# mcu.net
KiCad netlist of a schematic drawn in Altium Designer
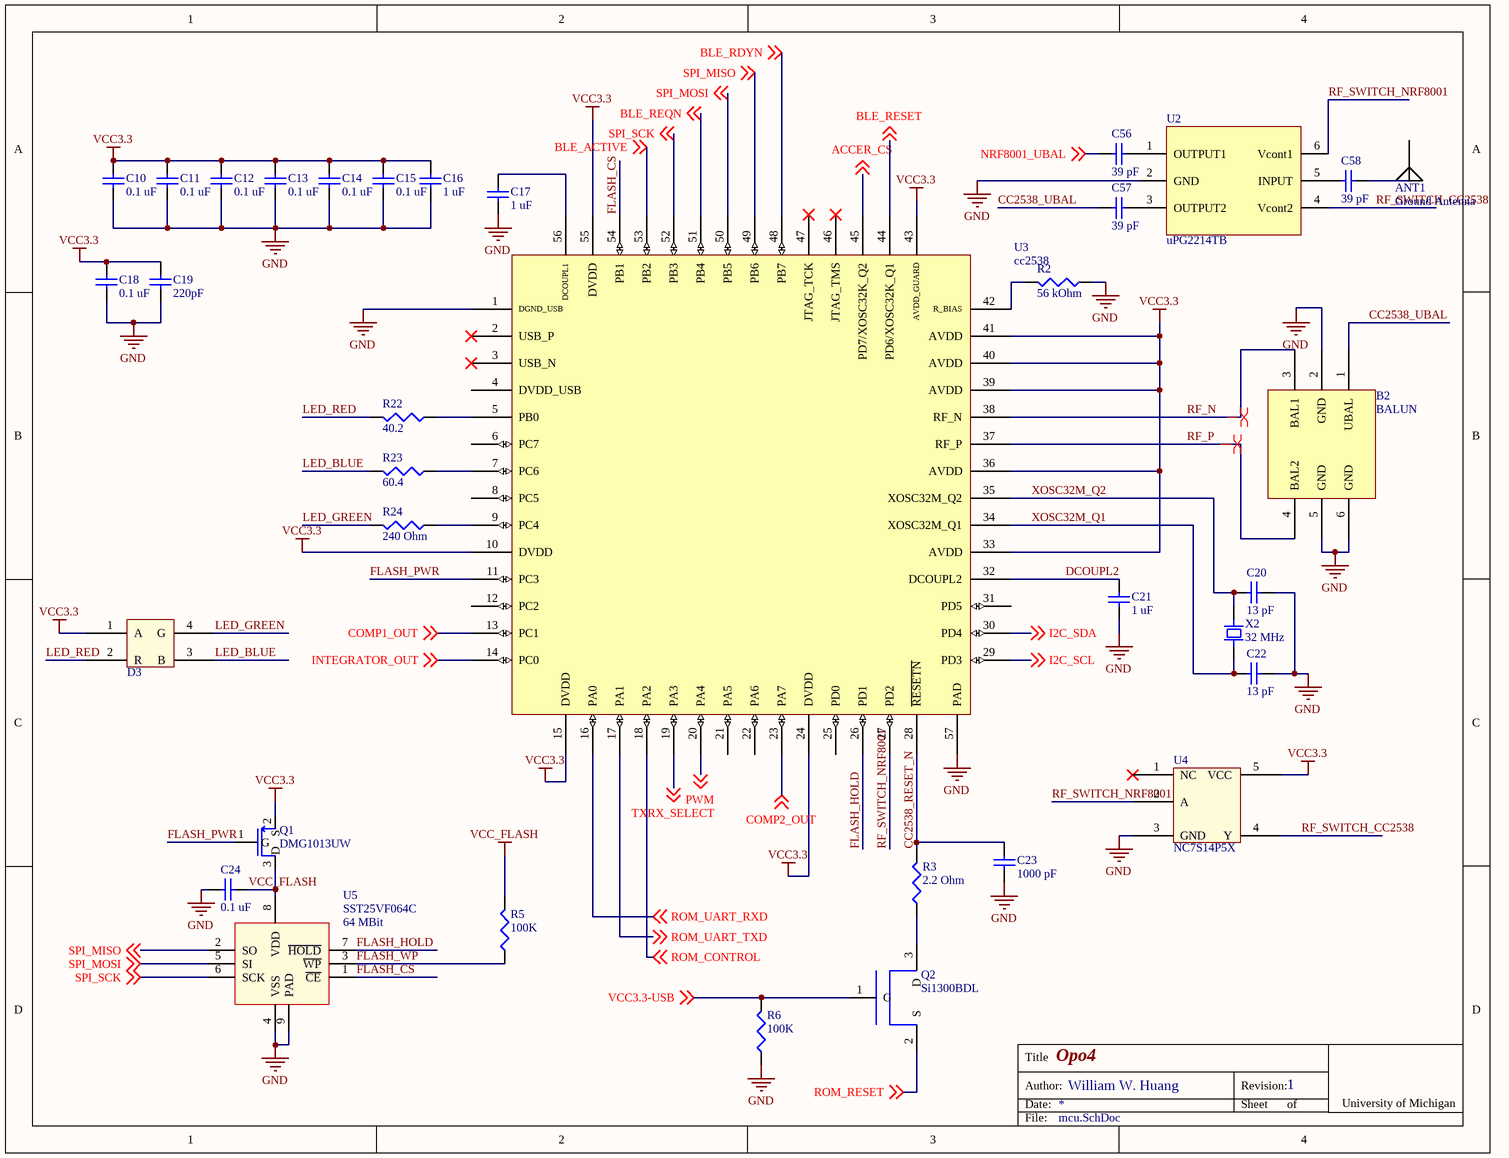
[diagram p0: mcu.SchDoc]

(export (version "E")
  (design (tool "Eeschema 10.0.6"))
  (components
    (comp (ref "ANT1")
      (value "Ground Antenna")
      (footprint "SMD Ground Antenna")
      (description "Molex 2.4 GHz SMD On-Ground Antenna")
      (libsource (lib "opo_general") (part "Molex Antenna"))
    )
    (comp (ref "B2")
      (value "BALUN")
      (footprint "2450BM15A0002")
      (description "Johanson CC253X Balun")
      (fields (field (name "MFR") "Johanson Technology") (field (name "MFR PART NUMBER") "2450BM15A0002"))
      (libsource (lib "opo_general") (part "cc2538_Balun"))
    )
    (comp (ref "C10")
      (value "0.1 uF")
      (footprint "0402")
      (description "Ceramic capacitor, 0.1u, 0402 package")
      (fields (field (name "TOLERANCE") "10%") (field (name "Comment") "Ceramic capacitor"))
      (libsource (lib "rlc") (part "C_0.1u_0402_ceramic"))
    )
    (comp (ref "C11")
      (value "0.1 uF")
      (footprint "0402")
      (description "Ceramic capacitor, 0.1u, 0402 package")
      (fields (field (name "TOLERANCE") "10%") (field (name "Comment") "Ceramic capacitor"))
      (libsource (lib "rlc") (part "C_0.1u_0402_ceramic"))
    )
    (comp (ref "C12")
      (value "0.1 uF")
      (footprint "0402")
      (description "Ceramic capacitor, 0.1u, 0402 package")
      (fields (field (name "TOLERANCE") "10%") (field (name "Comment") "Ceramic capacitor"))
      (libsource (lib "rlc") (part "C_0.1u_0402_ceramic"))
    )
    (comp (ref "C13")
      (value "0.1 uF")
      (footprint "0402")
      (description "Ceramic capacitor, 0.1u, 0402 package")
      (fields (field (name "TOLERANCE") "10%") (field (name "Comment") "Ceramic capacitor"))
      (libsource (lib "rlc") (part "C_0.1u_0402_ceramic"))
    )
    (comp (ref "C14")
      (value "0.1 uF")
      (footprint "0402")
      (description "Ceramic capacitor, 0.1u, 0402 package")
      (fields (field (name "TOLERANCE") "10%") (field (name "Comment") "Ceramic capacitor"))
      (libsource (lib "rlc") (part "C_0.1u_0402_ceramic"))
    )
    (comp (ref "C15")
      (value "0.1 uF")
      (footprint "0402")
      (description "Ceramic capacitor, 0.1u, 0402 package")
      (fields (field (name "TOLERANCE") "10%") (field (name "Comment") "Ceramic capacitor"))
      (libsource (lib "rlc") (part "C_0.1u_0402_ceramic"))
    )
    (comp (ref "C16")
      (value "1 uF")
      (footprint "0402")
      (description "Ceramic capacitor, 1 uF, 0402 package")
      (fields (field (name "TOLERANCE") "10%") (field (name "Comment") "Ceramic capacitor"))
      (libsource (lib "rlc") (part "C_1u_0402_ceramic"))
    )
    (comp (ref "C17")
      (value "1 uF")
      (footprint "0402")
      (description "Ceramic capacitor, 1 uF, 0402 package")
      (fields (field (name "TOLERANCE") "10%") (field (name "Comment") "Ceramic capacitor"))
      (libsource (lib "rlc") (part "C_1u_0402_ceramic"))
    )
    (comp (ref "C18")
      (value "0.1 uF")
      (footprint "0402")
      (description "Ceramic capacitor, 0.1u, 0402 package")
      (fields (field (name "TOLERANCE") "10%") (field (name "Comment") "Ceramic capacitor"))
      (libsource (lib "rlc") (part "C_0.1u_0402_ceramic"))
    )
    (comp (ref "C19")
      (value "220pF")
      (footprint "0402")
      (description "220pF 5% 50 V C0G NP0 0402 ceramic cap")
      (fields (field (name "MFR") "Murata") (field (name "MFR PART NUMBER") "GRM1555C1H221JA01D"))
      (libsource (lib "rlc") (part "C_220pf_0402_ceramic"))
    )
    (comp (ref "C20")
      (value "13 pF")
      (footprint "0402")
      (description "13pf, 50V, 2%, c0G, NP0, 0402, ceramic")
      (fields (field (name "MFR") "Murata") (field (name "MFR PART NUMBER") "GRM1555C1H130GA01D"))
      (libsource (lib "rlc") (part "C_13p_0402"))
    )
    (comp (ref "C21")
      (value "1 uF")
      (footprint "0402")
      (description "Ceramic capacitor, 1 uF, 0402 package")
      (fields (field (name "TOLERANCE") "10%") (field (name "Comment") "Ceramic capacitor"))
      (libsource (lib "rlc") (part "C_1u_0402_ceramic"))
    )
    (comp (ref "C22")
      (value "13 pF")
      (footprint "0402")
      (description "13pf, 50V, 2%, c0G, NP0, 0402, ceramic")
      (fields (field (name "MFR") "Murata") (field (name "MFR PART NUMBER") "GRM1555C1H130GA01D"))
      (libsource (lib "rlc") (part "C_13p_0402"))
    )
    (comp (ref "C23")
      (value "1000 pF")
      (footprint "0402")
      (description "Ceramic capacitor, 1000 pF, 0402 package")
      (fields (field (name "TOLERANCE") "10%") (field (name "Comment") "Ceramic capacitor"))
      (libsource (lib "rlc") (part "C_1000p_0402_ceramic"))
    )
    (comp (ref "C24")
      (value "0.1 uF")
      (footprint "0402")
      (description "Ceramic capacitor, 0.1u, 0402 package")
      (fields (field (name "TOLERANCE") "10%") (field (name "Comment") "Ceramic capacitor"))
      (libsource (lib "rlc") (part "C_0.1u_0402_ceramic"))
    )
    (comp (ref "C56")
      (value "39 pF")
      (footprint "0402")
      (description "Ceramic capacitor, 0402, 39 pF, 5%, C0G, NP0, RF suitable")
      (fields (field (name "Comment") "Ceramic Capacitor"))
      (libsource (lib "rlc") (part "C_39pf_0402_ceramic"))
    )
    (comp (ref "C57")
      (value "39 pF")
      (footprint "0402")
      (description "Ceramic capacitor, 0402, 39 pF, 5%, C0G, NP0, RF suitable")
      (fields (field (name "Comment") "Ceramic Capacitor"))
      (libsource (lib "rlc") (part "C_39pf_0402_ceramic"))
    )
    (comp (ref "C58")
      (value "39 pF")
      (footprint "0402")
      (description "Ceramic capacitor, 0402, 39 pF, 5%, C0G, NP0, RF suitable")
      (fields (field (name "Comment") "Ceramic Capacitor"))
      (libsource (lib "rlc") (part "C_39pf_0402_ceramic"))
    )
    (comp (ref "D3")
      (value "Tri Color LED")
      (footprint "0404")
      (description "LED, RGB, 0404")
      (libsource (lib "rlc") (part "D_LED_RGB_0404"))
    )
    (comp (ref "Q1")
      (value "DMG1013UW")
      (footprint "SC70-3")
      (description "P-CHANNEL ENHANCEMENT MODE MOSFET")
      (libsource (lib "opo_general") (part "DMG1013UW"))
    )
    (comp (ref "Q2")
      (value "Si1300BDL")
      (footprint "SC70-3")
      (description "MOSFET N-CH D-S 20V SC-70-3")
      (libsource (lib "opo_general") (part "Si1300BDL"))
    )
    (comp (ref "R2")
      (value "56 kOhm")
      (footprint "0402")
      (description "56 kOhm, 1%, .0603 W, 0402")
      (fields (field (name "MFR") "Rohm") (field (name "MFR PART NUMBER") "MCR01MRTF5602"))
      (libsource (lib "rlc") (part "R_56K_0402"))
    )
    (comp (ref "R3")
      (value "2.2 Ohm")
      (footprint "0402")
      (description "2.2 Ohm, 1%, .063W, 0402")
      (fields (field (name "MFR") "Vishay Dale") (field (name "MFR PART NUMBER") "CRCW04022R20FKED"))
      (libsource (lib "rlc") (part "R_2.2_0402"))
    )
    (comp (ref "R5")
      (value "100K")
      (footprint "0402")
      (description "Chip resistor, 100K, 0402 package")
      (fields (field (name "TOLERANCE") "1%") (field (name "POWER") "1/16 W"))
      (libsource (lib "rlc") (part "R_100K_0402"))
    )
    (comp (ref "R6")
      (value "100K")
      (footprint "0402")
      (description "Chip resistor, 100K, 0402 package")
      (fields (field (name "TOLERANCE") "1%") (field (name "POWER") "1/16 W"))
      (libsource (lib "rlc") (part "R_100K_0402"))
    )
    (comp (ref "R22")
      (value "40.2")
      (footprint "0201")
      (description "40.2 Ohm 0201 1% Chip Resistor")
      (fields (field (name "Comment") "Chip Resistor"))
      (libsource (lib "rlc") (part "R_40.2_0201"))
    )
    (comp (ref "R23")
      (value "60.4")
      (footprint "0201")
      (description "60.4 Ohm, .05W, 1% 0201 Chip Resistor")
      (fields (field (name "Comment") "Chip resistor"))
      (libsource (lib "rlc") (part "R_60.4_0201"))
    )
    (comp (ref "R24")
      (value "240 Ohm")
      (footprint "0201")
      (description "240 Ohm, 1%, .05W, 0201 Chip Resistor")
      (fields (field (name "Comment") "Chip resistor"))
      (libsource (lib "rlc") (part "R_240_0201"))
    )
    (comp (ref "U2")
      (value "uPG2214TB")
      (footprint "minimold-6")
      (description "GaAs Integrated Circuit for L, S-Band SPDT Switch")
      (libsource (lib "opo_general") (part "uPG2214TB"))
    )
    (comp (ref "U3")
      (value "cc2538")
      (footprint "QFN50P800X800X100_HS-57N")
      (description "cc2538 MCU/802.15.4 radio")
      (libsource (lib "opo_general") (part "cc2538"))
    )
    (comp (ref "U4")
      (value "NC7S14P5X")
      (footprint "SC70-5")
      (description "Single Inverter")
      (fields (field (name "MFR") "Fairchild"))
      (libsource (lib "opo_general") (part "NC7S14P5X"))
    )
    (comp (ref "U5")
      (value "SST25VF064C")
      (footprint "WSON")
      (description "64 Mbit SPI Serial Dual I/O Flash")
      (fields (field (name "CAPACITY") "64 MBit"))
      (libsource (lib "opo_general") (part "SST25VF064C"))
    )
    (comp (ref "X2")
      (value "32 MHz")
      (footprint "FA-128")
      (description "32MHz, 10ppm, 10pF, 60 Ohm")
      (fields (field (name "MFR") "Epson") (field (name "MFR PART NUMBER") "FA-128 32.0000MF20X-K3"))
      (libsource (lib "opo_general") (part "X_32M_FA-128"))
    )
  )
  (nets
    (net (code "1") (name "/CC2538_RESET_N") (class "Default")
      (node (ref "C23") (pin "1") (pintype "passive"))
      (node (ref "R3") (pin "1") (pintype "passive"))
      (node (ref "U3") (pin "28") (pinfunction "~{RESETN}_28") (pintype "passive"))
    )
    (net (code "2") (name "/CC2538_UBAL") (class "Default")
      (node (ref "B2") (pin "1") (pinfunction "UBAL_1") (pintype "passive"))
      (node (ref "C57") (pin "2") (pintype "passive"))
    )
    (net (code "3") (name "/DCOUPL2") (class "Default")
      (node (ref "C21") (pin "1") (pintype "passive"))
      (node (ref "U3") (pin "32") (pinfunction "DCOUPL2_32") (pintype "power_in"))
    )
    (net (code "4") (name "/FLASH_CS") (class "Default")
      (node (ref "U3") (pin "54") (pinfunction "PB1_54") (pintype "bidirectional"))
      (node (ref "U5") (pin "1") (pinfunction "~{CE}_1") (pintype "passive"))
    )
    (net (code "5") (name "/FLASH_HOLD") (class "Default")
      (node (ref "U3") (pin "26") (pinfunction "PD1_26") (pintype "bidirectional"))
      (node (ref "U5") (pin "7") (pinfunction "~{HOLD}_7") (pintype "passive"))
    )
    (net (code "6") (name "/FLASH_PWR") (class "Default")
      (node (ref "Q1") (pin "1") (pinfunction "G_1") (pintype "passive"))
      (node (ref "U3") (pin "11") (pinfunction "PC3_11") (pintype "bidirectional"))
    )
    (net (code "7") (name "/FLASH_WP") (class "Default")
      (node (ref "R5") (pin "2") (pintype "passive"))
      (node (ref "U5") (pin "3") (pinfunction "~{WP}_3") (pintype "passive"))
    )
    (net (code "8") (name "/LED_BLUE") (class "Default")
      (node (ref "D3") (pin "3") (pinfunction "B_3") (pintype "passive"))
      (node (ref "R23") (pin "1") (pintype "passive"))
    )
    (net (code "9") (name "/LED_GREEN") (class "Default")
      (node (ref "D3") (pin "4") (pinfunction "G_4") (pintype "passive"))
      (node (ref "R24") (pin "1") (pintype "passive"))
    )
    (net (code "10") (name "/LED_RED") (class "Default")
      (node (ref "D3") (pin "2") (pinfunction "R_2") (pintype "passive"))
      (node (ref "R22") (pin "1") (pintype "passive"))
    )
    (net (code "11") (name "/RF_N") (class "Default")
      (node (ref "B2") (pin "3") (pinfunction "BAL1_3") (pintype "passive"))
      (node (ref "U3") (pin "38") (pinfunction "RF_N_38") (pintype "passive"))
    )
    (net (code "12") (name "/RF_P") (class "Default")
      (node (ref "B2") (pin "4") (pinfunction "BAL2_4") (pintype "passive"))
      (node (ref "U3") (pin "37") (pinfunction "RF_P_37") (pintype "passive"))
    )
    (net (code "13") (name "/RF_SWITCH_CC2538") (class "Default")
      (node (ref "U2") (pin "4") (pinfunction "Vcont2_4") (pintype "power_in"))
      (node (ref "U4") (pin "4") (pinfunction "Y_4") (pintype "passive"))
    )
    (net (code "14") (name "/RF_SWITCH_NRF8001") (class "Default")
      (node (ref "U2") (pin "6") (pinfunction "Vcont1_6") (pintype "power_in"))
      (node (ref "U3") (pin "27") (pinfunction "PD2_27") (pintype "bidirectional"))
      (node (ref "U4") (pin "2") (pinfunction "A_2") (pintype "passive"))
    )
    (net (code "15") (name "/XOSC32M_Q1") (class "Default")
      (node (ref "C22") (pin "2") (pintype "passive"))
      (node (ref "U3") (pin "34") (pinfunction "XOSC32M_Q1_34") (pintype "passive"))
      (node (ref "X2") (pin "3") (pintype "passive"))
    )
    (net (code "16") (name "/XOSC32M_Q2") (class "Default")
      (node (ref "C20") (pin "1") (pintype "passive"))
      (node (ref "U3") (pin "35") (pinfunction "XOSC32M_Q2_35") (pintype "passive"))
      (node (ref "X2") (pin "1") (pintype "passive"))
    )
    (net (code "17") (name "ACCER_CS") (class "Default")
      (node (ref "U3") (pin "45") (pinfunction "PD7/XOSC32K_Q2_45") (pintype "passive"))
    )
    (net (code "18") (name "BLE_ACTIVE") (class "Default")
      (node (ref "U3") (pin "53") (pinfunction "PB2_53") (pintype "bidirectional"))
    )
    (net (code "19") (name "BLE_RDYN") (class "Default")
      (node (ref "U3") (pin "48") (pinfunction "PB7_48") (pintype "bidirectional"))
    )
    (net (code "20") (name "BLE_REQN") (class "Default")
      (node (ref "U3") (pin "51") (pinfunction "PB4_51") (pintype "bidirectional"))
    )
    (net (code "21") (name "BLE_RESET") (class "Default")
      (node (ref "U3") (pin "44") (pinfunction "PD6/XOSC32K_Q1_44") (pintype "passive"))
    )
    (net (code "22") (name "COMP1_OUT") (class "Default")
      (node (ref "U3") (pin "13") (pinfunction "PC1_13") (pintype "bidirectional"))
    )
    (net (code "23") (name "COMP2_OUT") (class "Default")
      (node (ref "U3") (pin "23") (pinfunction "PA7_23") (pintype "bidirectional"))
    )
    (net (code "24") (name "GND") (class "Default")
      (node (ref "B2") (pin "2") (pinfunction "GND_2") (pintype "passive"))
      (node (ref "B2") (pin "5") (pinfunction "GND_5") (pintype "passive"))
      (node (ref "B2") (pin "6") (pinfunction "GND_6") (pintype "passive"))
      (node (ref "C10") (pin "2") (pintype "passive"))
      (node (ref "C11") (pin "2") (pintype "passive"))
      (node (ref "C12") (pin "2") (pintype "passive"))
      (node (ref "C13") (pin "2") (pintype "passive"))
      (node (ref "C14") (pin "2") (pintype "passive"))
      (node (ref "C15") (pin "2") (pintype "passive"))
      (node (ref "C16") (pin "2") (pintype "passive"))
      (node (ref "C17") (pin "2") (pintype "passive"))
      (node (ref "C18") (pin "2") (pintype "passive"))
      (node (ref "C19") (pin "2") (pintype "passive"))
      (node (ref "C20") (pin "2") (pintype "passive"))
      (node (ref "C21") (pin "2") (pintype "passive"))
      (node (ref "C22") (pin "1") (pintype "passive"))
      (node (ref "C23") (pin "2") (pintype "passive"))
      (node (ref "C24") (pin "1") (pintype "passive"))
      (node (ref "R2") (pin "2") (pintype "passive"))
      (node (ref "R6") (pin "2") (pintype "passive"))
      (node (ref "U2") (pin "2") (pinfunction "GND_2") (pintype "power_in"))
      (node (ref "U3") (pin "1") (pinfunction "DGND_USB_1") (pintype "passive"))
      (node (ref "U3") (pin "57") (pinfunction "PAD_57") (pintype "passive"))
      (node (ref "U4") (pin "3") (pinfunction "GND_3") (pintype "passive"))
      (node (ref "U5") (pin "4") (pinfunction "VSS_4") (pintype "passive"))
      (node (ref "U5") (pin "9") (pinfunction "PAD_9") (pintype "passive"))
    )
    (net (code "25") (name "I2C_SCL") (class "Default")
      (node (ref "U3") (pin "29") (pinfunction "PD3_29") (pintype "bidirectional"))
    )
    (net (code "26") (name "I2C_SDA") (class "Default")
      (node (ref "U3") (pin "30") (pinfunction "PD4_30") (pintype "bidirectional"))
    )
    (net (code "27") (name "INTEGRATOR_OUT") (class "Default")
      (node (ref "U3") (pin "14") (pinfunction "PC0_14") (pintype "bidirectional"))
    )
    (net (code "28") (name "NRF8001_UBAL") (class "Default") (node (ref "C56") (pin "1") (pintype "passive")))
    (net (code "29") (name "Net-(Q2-D)") (class "Default")
      (node (ref "Q2") (pin "3") (pinfunction "D_3") (pintype "passive"))
      (node (ref "R3") (pin "2") (pintype "passive"))
    )
    (net (code "30") (name "Net-(U2-INPUT)") (class "Default")
      (node (ref "C58") (pin "1") (pintype "passive"))
      (node (ref "U2") (pin "5") (pinfunction "INPUT_5") (pintype "power_in"))
    )
    (net (code "31") (name "Net-(U2-OUTPUT1)") (class "Default")
      (node (ref "C56") (pin "2") (pintype "passive"))
      (node (ref "U2") (pin "1") (pinfunction "OUTPUT1_1") (pintype "power_in"))
    )
    (net (code "32") (name "Net-(U2-OUTPUT2)") (class "Default")
      (node (ref "C57") (pin "1") (pintype "passive"))
      (node (ref "U2") (pin "3") (pinfunction "OUTPUT2_3") (pintype "power_in"))
    )
    (net (code "33") (name "Net-(U3-DCOUPL1)") (class "Default")
      (node (ref "C17") (pin "1") (pintype "passive"))
      (node (ref "U3") (pin "56") (pinfunction "DCOUPL1_56") (pintype "power_in"))
    )
    (net (code "34") (name "Net-(U3-PB0)") (class "Default")
      (node (ref "R22") (pin "2") (pintype "passive"))
      (node (ref "U3") (pin "5") (pinfunction "PB0_5") (pintype "passive"))
    )
    (net (code "35") (name "Net-(U3-PC4)") (class "Default")
      (node (ref "R24") (pin "2") (pintype "passive"))
      (node (ref "U3") (pin "9") (pinfunction "PC4_9") (pintype "bidirectional"))
    )
    (net (code "36") (name "Net-(U3-PC6)") (class "Default")
      (node (ref "R23") (pin "2") (pintype "passive"))
      (node (ref "U3") (pin "7") (pinfunction "PC6_7") (pintype "bidirectional"))
    )
    (net (code "37") (name "Net-(U3-R_BIAS)") (class "Default")
      (node (ref "R2") (pin "1") (pintype "passive"))
      (node (ref "U3") (pin "42") (pinfunction "R_BIAS_42") (pintype "passive"))
    )
    (net (code "38") (name "PWM") (class "Default")
      (node (ref "U3") (pin "20") (pinfunction "PA4_20") (pintype "bidirectional"))
    )
    (net (code "39") (name "ROM_CONTROL") (class "Default")
      (node (ref "U3") (pin "18") (pinfunction "PA2_18") (pintype "bidirectional"))
    )
    (net (code "40") (name "ROM_RESET") (class "Default")
      (node (ref "Q2") (pin "2") (pinfunction "S_2") (pintype "passive"))
    )
    (net (code "41") (name "ROM_UART_RXD") (class "Default")
      (node (ref "U3") (pin "16") (pinfunction "PA0_16") (pintype "bidirectional"))
    )
    (net (code "42") (name "ROM_UART_TXD") (class "Default")
      (node (ref "U3") (pin "17") (pinfunction "PA1_17") (pintype "bidirectional"))
    )
    (net (code "43") (name "SPI_MISO") (class "Default")
      (node (ref "U3") (pin "49") (pinfunction "PB6_49") (pintype "bidirectional"))
      (node (ref "U5") (pin "2") (pinfunction "SO_2") (pintype "passive"))
    )
    (net (code "44") (name "SPI_MOSI") (class "Default")
      (node (ref "U3") (pin "50") (pinfunction "PB5_50") (pintype "bidirectional"))
      (node (ref "U5") (pin "5") (pinfunction "SI_5") (pintype "passive"))
    )
    (net (code "45") (name "SPI_SCK") (class "Default")
      (node (ref "U3") (pin "52") (pinfunction "PB3_52") (pintype "bidirectional"))
      (node (ref "U5") (pin "6") (pinfunction "SCK_6") (pintype "passive"))
    )
    (net (code "46") (name "TXRX_SELECT") (class "Default")
      (node (ref "U3") (pin "19") (pinfunction "PA3_19") (pintype "bidirectional"))
    )
    (net (code "47") (name "VCC3.3") (class "Default")
      (node (ref "C10") (pin "1") (pintype "passive"))
      (node (ref "C11") (pin "1") (pintype "passive"))
      (node (ref "C12") (pin "1") (pintype "passive"))
      (node (ref "C13") (pin "1") (pintype "passive"))
      (node (ref "C14") (pin "1") (pintype "passive"))
      (node (ref "C15") (pin "1") (pintype "passive"))
      (node (ref "C16") (pin "1") (pintype "passive"))
      (node (ref "C18") (pin "1") (pintype "passive"))
      (node (ref "C19") (pin "1") (pintype "passive"))
      (node (ref "D3") (pin "1") (pinfunction "A_1") (pintype "passive"))
      (node (ref "Q1") (pin "2") (pinfunction "S_2") (pintype "passive"))
      (node (ref "U3") (pin "10") (pinfunction "DVDD_10") (pintype "power_in"))
      (node (ref "U3") (pin "15") (pinfunction "DVDD_15") (pintype "power_in"))
      (node (ref "U3") (pin "24") (pinfunction "DVDD_24") (pintype "power_in"))
      (node (ref "U3") (pin "33") (pinfunction "AVDD_33") (pintype "power_in"))
      (node (ref "U3") (pin "36") (pinfunction "AVDD_36") (pintype "power_in"))
      (node (ref "U3") (pin "39") (pinfunction "AVDD_39") (pintype "power_in"))
      (node (ref "U3") (pin "40") (pinfunction "AVDD_40") (pintype "power_in"))
      (node (ref "U3") (pin "41") (pinfunction "AVDD_41") (pintype "power_in"))
      (node (ref "U3") (pin "43") (pinfunction "AVDD_GUARD_43") (pintype "power_in"))
      (node (ref "U3") (pin "55") (pinfunction "DVDD_55") (pintype "power_in"))
      (node (ref "U4") (pin "5") (pinfunction "VCC_5") (pintype "passive"))
    )
    (net (code "48") (name "VCC3.3-USB") (class "Default")
      (node (ref "Q2") (pin "1") (pinfunction "G_1") (pintype "passive"))
      (node (ref "R6") (pin "1") (pintype "passive"))
    )
    (net (code "49") (name "VCC_FLASH") (class "Default")
      (node (ref "C24") (pin "2") (pintype "passive"))
      (node (ref "Q1") (pin "3") (pinfunction "D_3") (pintype "passive"))
      (node (ref "R5") (pin "1") (pintype "passive"))
      (node (ref "U5") (pin "8") (pinfunction "VDD_8") (pintype "passive"))
    )
    (net (code "50") (name "unconnected-(ANT1-Pad1)") (class "Default")
      (node (ref "ANT1") (pin "1") (pintype "passive"))
    )
    (net (code "51") (name "unconnected-(C58-Pad2)") (class "Default")
      (node (ref "C58") (pin "2") (pintype "passive"))
    )
    (net (code "52") (name "unconnected-(U3-DVDD_USB-Pad4)") (class "Default")
      (node (ref "U3") (pin "4") (pinfunction "DVDD_USB_4") (pintype "passive"))
    )
    (net (code "53") (name "unconnected-(U3-JTAG_TCK-Pad47)") (class "Default")
      (node (ref "U3") (pin "47") (pinfunction "JTAG_TCK_47") (pintype "passive+no_connect"))
    )
    (net (code "54") (name "unconnected-(U3-JTAG_TMS-Pad46)") (class "Default")
      (node (ref "U3") (pin "46") (pinfunction "JTAG_TMS_46") (pintype "passive+no_connect"))
    )
    (net (code "55") (name "unconnected-(U3-PA5-Pad21)") (class "Default")
      (node (ref "U3") (pin "21") (pinfunction "PA5_21") (pintype "bidirectional"))
    )
    (net (code "56") (name "unconnected-(U3-PA6-Pad22)") (class "Default")
      (node (ref "U3") (pin "22") (pinfunction "PA6_22") (pintype "bidirectional"))
    )
    (net (code "57") (name "unconnected-(U3-PC2-Pad12)") (class "Default")
      (node (ref "U3") (pin "12") (pinfunction "PC2_12") (pintype "bidirectional"))
    )
    (net (code "58") (name "unconnected-(U3-PC5-Pad8)") (class "Default")
      (node (ref "U3") (pin "8") (pinfunction "PC5_8") (pintype "bidirectional"))
    )
    (net (code "59") (name "unconnected-(U3-PC7-Pad6)") (class "Default")
      (node (ref "U3") (pin "6") (pinfunction "PC7_6") (pintype "bidirectional"))
    )
    (net (code "60") (name "unconnected-(U3-PD0-Pad25)") (class "Default")
      (node (ref "U3") (pin "25") (pinfunction "PD0_25") (pintype "bidirectional"))
    )
    (net (code "61") (name "unconnected-(U3-PD5-Pad31)") (class "Default")
      (node (ref "U3") (pin "31") (pinfunction "PD5_31") (pintype "bidirectional"))
    )
    (net (code "62") (name "unconnected-(U3-USB_N-Pad3)") (class "Default")
      (node (ref "U3") (pin "3") (pinfunction "USB_N_3") (pintype "passive+no_connect"))
    )
    (net (code "63") (name "unconnected-(U3-USB_P-Pad2)") (class "Default")
      (node (ref "U3") (pin "2") (pinfunction "USB_P_2") (pintype "passive+no_connect"))
    )
    (net (code "64") (name "unconnected-(U4-NC-Pad1)") (class "Default")
      (node (ref "U4") (pin "1") (pinfunction "NC_1") (pintype "passive+no_connect"))
    )
  )
)
